# mcu_stm32h563.net
KiCad netlist of a schematic drawn in Altium Designer
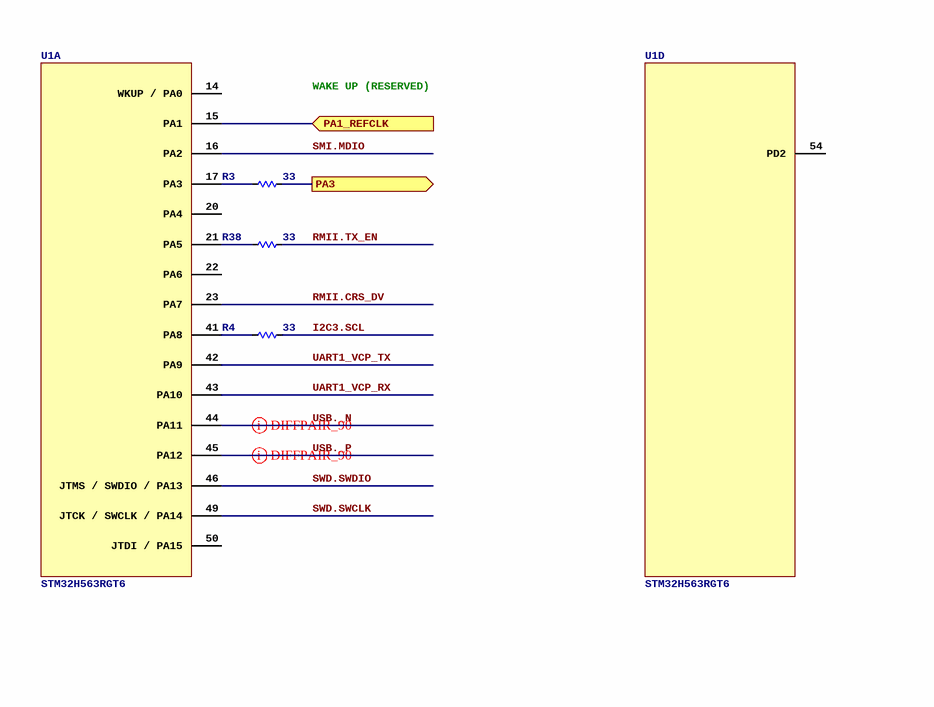
[diagram p0: mcu_stm32h563.SchDoc, top left]
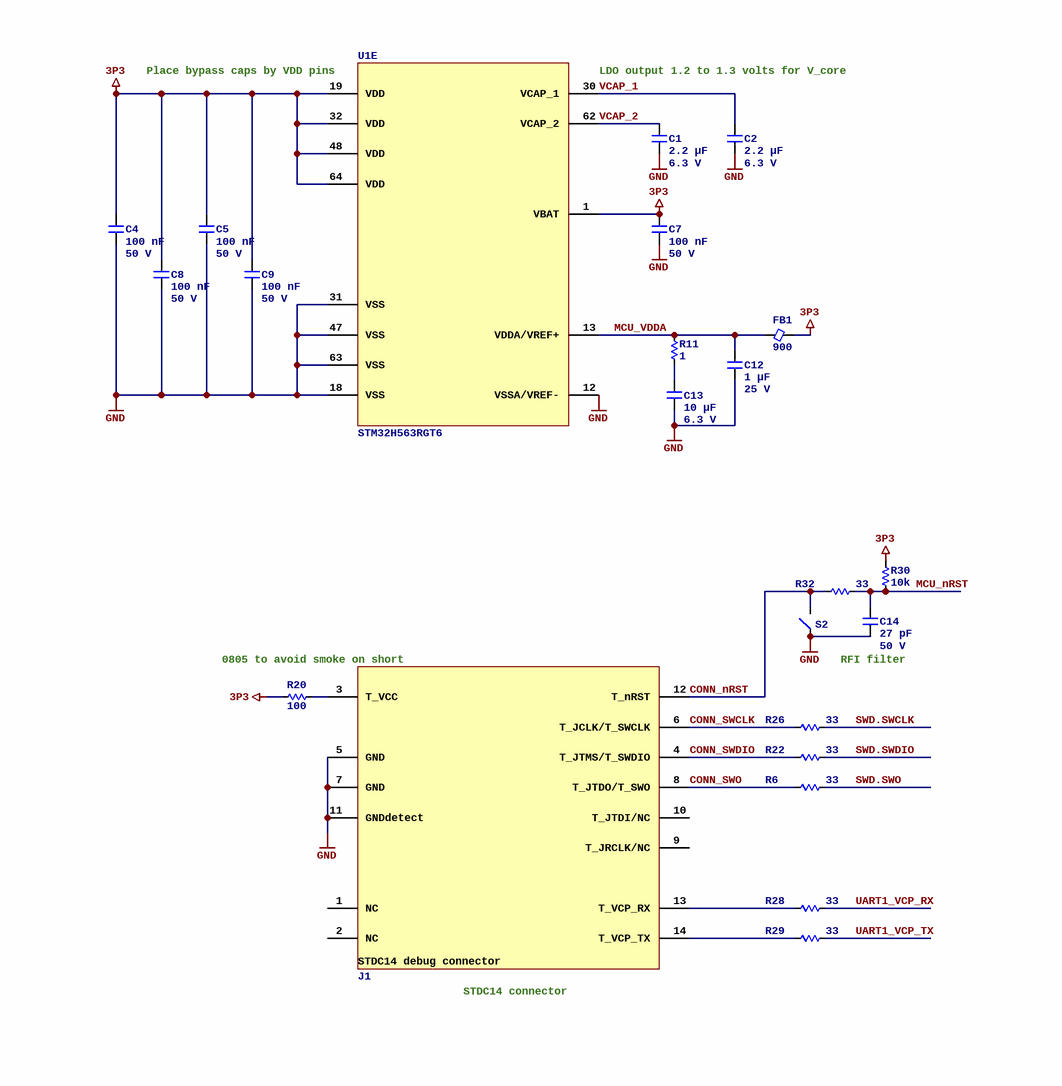
[diagram p1: mcu_stm32h563.SchDoc, top right]
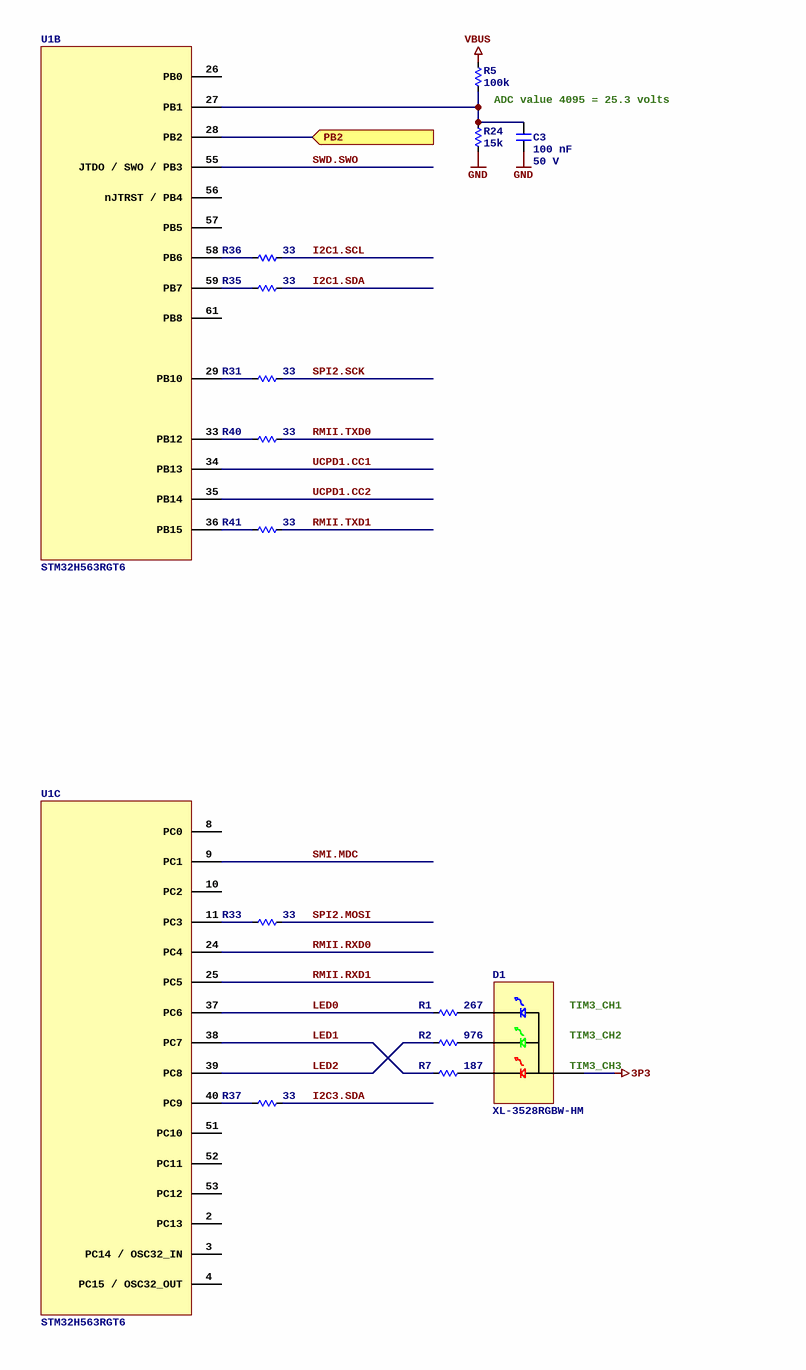
[diagram p2: mcu_stm32h563.SchDoc, bottom left]
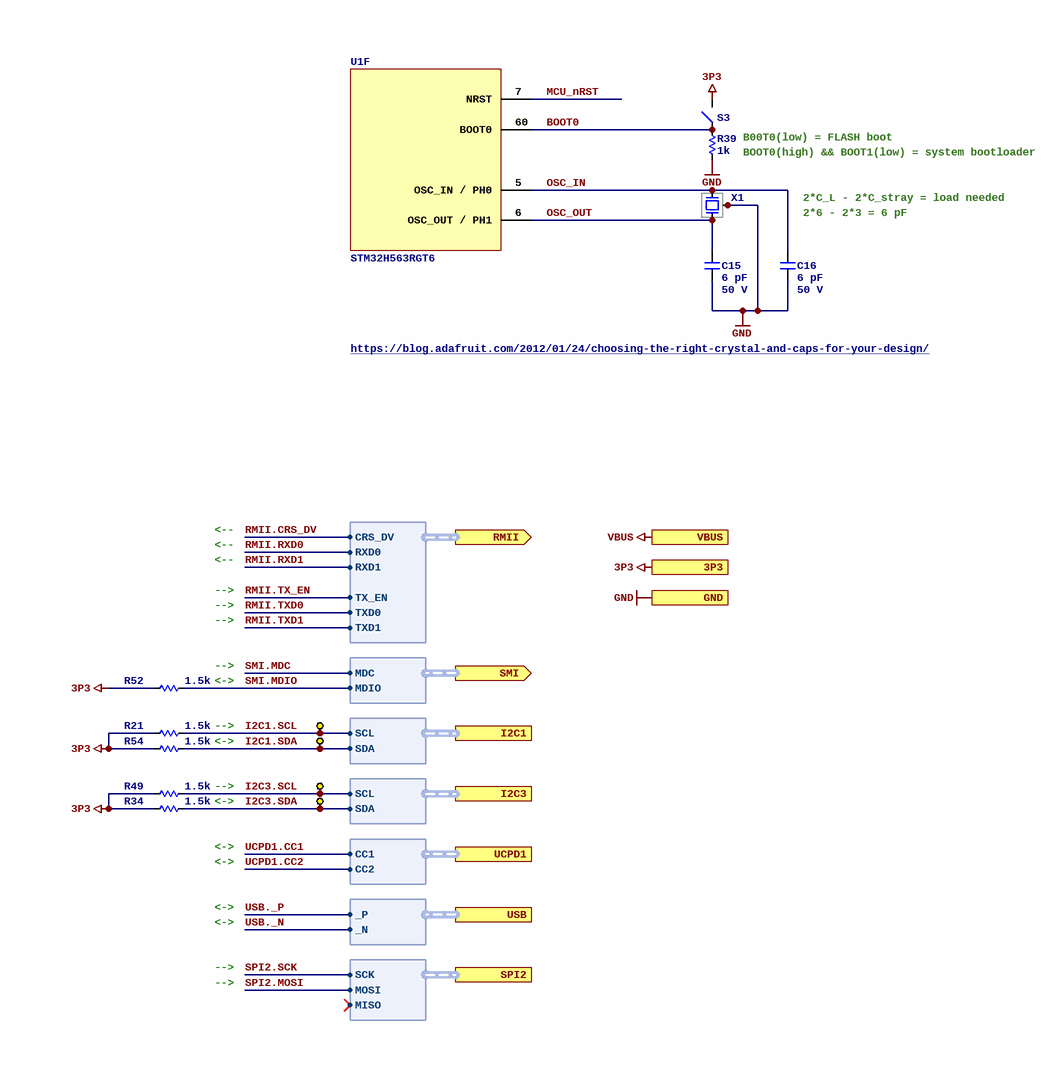
[diagram p3: mcu_stm32h563.SchDoc, bottom right]

(export (version "E")
  (design (tool "Eeschema 10.0.6"))
  (components
    (comp (ref "C1")
      (value "GCM188R70J225KE22D")
      (footprint "C0603")
      (fields
        (field (name "CAPACITANCE") "2.2 µF")
        (field (name "MANUFACTURER") "Murata Electronics")
        (field (name "VOLTAGE RATING") "6.3 V")
      )
      (libsource (lib "database") (part "__template_cap"))
    )
    (comp (ref "C2")
      (value "GCM188R70J225KE22D")
      (footprint "C0603")
      (fields
        (field (name "CAPACITANCE") "2.2 µF")
        (field (name "MANUFACTURER") "Murata Electronics")
        (field (name "VOLTAGE RATING") "6.3 V")
      )
      (libsource (lib "database") (part "__template_cap"))
    )
    (comp (ref "C3")
      (value "CL05B104KB54PNC")
      (footprint "C0402")
      (fields
        (field (name "CAPACITANCE") "100 nF")
        (field (name "MANUFACTURER") "Samsung Electro-Mechanics")
        (field (name "VOLTAGE RATING") "50 V")
      )
      (libsource (lib "database") (part "__template_cap"))
    )
    (comp (ref "C4")
      (value "CL05B104KB54PNC")
      (footprint "C0402")
      (fields
        (field (name "CAPACITANCE") "100 nF")
        (field (name "MANUFACTURER") "Samsung Electro-Mechanics")
        (field (name "VOLTAGE RATING") "50 V")
      )
      (libsource (lib "database") (part "__template_cap"))
    )
    (comp (ref "C5")
      (value "CL05B104KB54PNC")
      (footprint "C0402")
      (fields
        (field (name "CAPACITANCE") "100 nF")
        (field (name "MANUFACTURER") "Samsung Electro-Mechanics")
        (field (name "VOLTAGE RATING") "50 V")
      )
      (libsource (lib "database") (part "__template_cap"))
    )
    (comp (ref "C7")
      (value "CL05B104KB54PNC")
      (footprint "C0402")
      (fields
        (field (name "CAPACITANCE") "100 nF")
        (field (name "MANUFACTURER") "Samsung Electro-Mechanics")
        (field (name "VOLTAGE RATING") "50 V")
      )
      (libsource (lib "database") (part "__template_cap"))
    )
    (comp (ref "C8")
      (value "CL05B104KB54PNC")
      (footprint "C0402")
      (fields
        (field (name "CAPACITANCE") "100 nF")
        (field (name "MANUFACTURER") "Samsung Electro-Mechanics")
        (field (name "VOLTAGE RATING") "50 V")
      )
      (libsource (lib "database") (part "__template_cap"))
    )
    (comp (ref "C9")
      (value "CL05B104KB54PNC")
      (footprint "C0402")
      (fields
        (field (name "CAPACITANCE") "100 nF")
        (field (name "MANUFACTURER") "Samsung Electro-Mechanics")
        (field (name "VOLTAGE RATING") "50 V")
      )
      (libsource (lib "database") (part "__template_cap"))
    )
    (comp (ref "C12")
      (value "CL10B105KA8NNNC")
      (footprint "C0603")
      (fields
        (field (name "CAPACITANCE") "1 µF")
        (field (name "MANUFACTURER") "Samsung Electro-Mechanics")
        (field (name "VOLTAGE RATING") "25 V")
      )
      (libsource (lib "database") (part "__template_cap"))
    )
    (comp (ref "C13")
      (value "CC0805KKX7R5BB106")
      (footprint "C0805")
      (fields
        (field (name "CAPACITANCE") "10 µF")
        (field (name "MANUFACTURER") "YAGEO")
        (field (name "VOLTAGE RATING") "6.3 V")
      )
      (libsource (lib "database") (part "__template_cap"))
    )
    (comp (ref "C14")
      (value "CC0402JRNPO9BN270")
      (footprint "C0402")
      (fields
        (field (name "CAPACITANCE") "27 pF")
        (field (name "MANUFACTURER") "YAGEO")
        (field (name "VOLTAGE RATING") "50 V")
      )
      (libsource (lib "database") (part "__template_cap"))
    )
    (comp (ref "C15")
      (value "CC0402CRNPO9BN6R0")
      (footprint "C0402")
      (fields
        (field (name "CAPACITANCE") "6 pF")
        (field (name "MANUFACTURER") "YAGEO")
        (field (name "VOLTAGE RATING") "50 V")
      )
      (libsource (lib "database") (part "__template_cap"))
    )
    (comp (ref "C16")
      (value "CC0402CRNPO9BN6R0")
      (footprint "C0402")
      (fields
        (field (name "CAPACITANCE") "6 pF")
        (field (name "MANUFACTURER") "YAGEO")
        (field (name "VOLTAGE RATING") "50 V")
      )
      (libsource (lib "database") (part "__template_cap"))
    )
    (comp (ref "D1")
      (value "XL-3528RGBW-HM")
      (footprint "LED_RGB_SMD3528-4P")
      (description "LED Multi-Color Chip Red/Green/Blue 4-Pin PLCC T/R")
      (fields (field (name "MANUFACTURER") "XINGLIGHT"))
      (libsource (lib "database") (part "XL-3528RGBW-HM"))
    )
    (comp (ref "FB1")
      (value "BLM15PX601SN1D")
      (footprint "FB0402")
      (fields (field (name "MANUFACTURER") "Murata Electronics") (field (name "CURRENT RATING (MA)") "900"))
      (libsource (lib "database") (part "__template_fb"))
    )
    (comp (ref "J1")
      (value "FTSH-107-01-L-DV-K-A")
      (footprint "SAMTEC_FTSH-107-01-L-DV-K-A")
      (description "Connector Header Surface Mount 14 position 0.050\" (1.27mm)")
      (fields (field (name "MANUFACTURER") "Samtec"))
      (libsource (lib "database") (part "FTSH-107-01-L-DV-K-A"))
    )
    (comp (ref "R1")
      (value "267")
      (footprint "R0402")
      (fields
        (field (name "TOLERANCE") "1%")
        (field (name "MANUFACTURER PART NUMBER") "FRC0402F2670TS")
        (field (name "MANUFACTURER") "FOJAN")
      )
      (libsource (lib "database") (part "__template_resistor"))
    )
    (comp (ref "R2")
      (value "976")
      (footprint "R0402")
      (fields
        (field (name "TOLERANCE") "1%")
        (field (name "MANUFACTURER PART NUMBER") "RTT029760FTH")
        (field (name "MANUFACTURER") "RALEC")
      )
      (libsource (lib "database") (part "__template_resistor"))
    )
    (comp (ref "R3")
      (value "33")
      (footprint "R0402")
      (fields
        (field (name "TOLERANCE") "1%")
        (field (name "MANUFACTURER PART NUMBER") "CRCW040233R0FKED")
        (field (name "MANUFACTURER") "Vishay Intertech")
      )
      (libsource (lib "database") (part "__template_resistor"))
    )
    (comp (ref "R4")
      (value "33")
      (footprint "R0402")
      (fields
        (field (name "TOLERANCE") "1%")
        (field (name "MANUFACTURER PART NUMBER") "CRCW040233R0FKED")
        (field (name "MANUFACTURER") "Vishay Intertech")
      )
      (libsource (lib "database") (part "__template_resistor"))
    )
    (comp (ref "R5")
      (value "100k")
      (footprint "R0402")
      (fields
        (field (name "MANUFACTURER PART NUMBER") "0402WGF1003TCE")
        (field (name "MANUFACTURER") "UNI-ROYAL(Uniroyal Elec)")
        (field (name "TOLERANCE") "1%")
      )
      (libsource (lib "database") (part "__template_resistor"))
    )
    (comp (ref "R6")
      (value "33")
      (footprint "R0402")
      (fields
        (field (name "TOLERANCE") "1%")
        (field (name "MANUFACTURER PART NUMBER") "CRCW040233R0FKED")
        (field (name "MANUFACTURER") "Vishay Intertech")
      )
      (libsource (lib "database") (part "__template_resistor"))
    )
    (comp (ref "R7")
      (value "187")
      (footprint "R0402")
      (fields
        (field (name "TOLERANCE") "1%")
        (field (name "MANUFACTURER PART NUMBER") "ERJ2RKF1870X")
        (field (name "MANUFACTURER") "PANASONIC")
      )
      (libsource (lib "database") (part "__template_resistor"))
    )
    (comp (ref "R11")
      (value "1")
      (footprint "R0402")
      (fields
        (field (name "TOLERANCE") "1%")
        (field (name "MANUFACTURER PART NUMBER") "CRCW04021R00FKEDC")
        (field (name "MANUFACTURER") "Vishay Intertech")
      )
      (libsource (lib "database") (part "__template_resistor"))
    )
    (comp (ref "R20")
      (value "100")
      (footprint "R0805")
      (fields
        (field (name "TOLERANCE") "1%")
        (field (name "MANUFACTURER PART NUMBER") "AR05FTC1000")
        (field (name "MANUFACTURER") "Viking Tech")
      )
      (libsource (lib "database") (part "__template_resistor"))
    )
    (comp (ref "R21")
      (value "1.5k")
      (footprint "R0402")
      (fields
        (field (name "TOLERANCE") "1%")
        (field (name "MANUFACTURER PART NUMBER") "0402WGF1501TCE")
        (field (name "MANUFACTURER") "UNI-ROYAL(Uniroyal Elec)")
      )
      (libsource (lib "database") (part "__template_resistor"))
    )
    (comp (ref "R22")
      (value "33")
      (footprint "R0402")
      (fields
        (field (name "TOLERANCE") "1%")
        (field (name "MANUFACTURER PART NUMBER") "CRCW040233R0FKED")
        (field (name "MANUFACTURER") "Vishay Intertech")
      )
      (libsource (lib "database") (part "__template_resistor"))
    )
    (comp (ref "R24")
      (value "15k")
      (footprint "R0402")
      (fields
        (field (name "MANUFACTURER PART NUMBER") "0402WGF1502TCE")
        (field (name "MANUFACTURER") "UNI-ROYAL(Uniroyal Elec)")
        (field (name "TOLERANCE") "1%")
      )
      (libsource (lib "database") (part "__template_resistor"))
    )
    (comp (ref "R26")
      (value "33")
      (footprint "R0402")
      (fields
        (field (name "TOLERANCE") "1%")
        (field (name "MANUFACTURER PART NUMBER") "CRCW040233R0FKED")
        (field (name "MANUFACTURER") "Vishay Intertech")
      )
      (libsource (lib "database") (part "__template_resistor"))
    )
    (comp (ref "R28")
      (value "33")
      (footprint "R0402")
      (fields
        (field (name "TOLERANCE") "1%")
        (field (name "MANUFACTURER PART NUMBER") "CRCW040233R0FKED")
        (field (name "MANUFACTURER") "Vishay Intertech")
      )
      (libsource (lib "database") (part "__template_resistor"))
    )
    (comp (ref "R29")
      (value "33")
      (footprint "R0402")
      (fields
        (field (name "TOLERANCE") "1%")
        (field (name "MANUFACTURER PART NUMBER") "CRCW040233R0FKED")
        (field (name "MANUFACTURER") "Vishay Intertech")
      )
      (libsource (lib "database") (part "__template_resistor"))
    )
    (comp (ref "R30")
      (value "10k")
      (footprint "R0402")
      (fields
        (field (name "TOLERANCE") "1%")
        (field (name "MANUFACTURER PART NUMBER") "0402WGF1002TCE")
        (field (name "MANUFACTURER") "UNI-ROYAL(Uniroyal Elec)")
      )
      (libsource (lib "database") (part "__template_resistor"))
    )
    (comp (ref "R31")
      (value "33")
      (footprint "R0402")
      (fields
        (field (name "TOLERANCE") "1%")
        (field (name "MANUFACTURER PART NUMBER") "CRCW040233R0FKED")
        (field (name "MANUFACTURER") "Vishay Intertech")
      )
      (libsource (lib "database") (part "__template_resistor"))
    )
    (comp (ref "R32")
      (value "33")
      (footprint "R0402")
      (fields
        (field (name "TOLERANCE") "1%")
        (field (name "MANUFACTURER PART NUMBER") "CRCW040233R0FKED")
        (field (name "MANUFACTURER") "Vishay Intertech")
      )
      (libsource (lib "database") (part "__template_resistor"))
    )
    (comp (ref "R33")
      (value "33")
      (footprint "R0402")
      (fields
        (field (name "TOLERANCE") "1%")
        (field (name "MANUFACTURER PART NUMBER") "CRCW040233R0FKED")
        (field (name "MANUFACTURER") "Vishay Intertech")
      )
      (libsource (lib "database") (part "__template_resistor"))
    )
    (comp (ref "R34")
      (value "1.5k")
      (footprint "R0402")
      (fields
        (field (name "TOLERANCE") "1%")
        (field (name "MANUFACTURER PART NUMBER") "0402WGF1501TCE")
        (field (name "MANUFACTURER") "UNI-ROYAL(Uniroyal Elec)")
      )
      (libsource (lib "database") (part "__template_resistor"))
    )
    (comp (ref "R35")
      (value "33")
      (footprint "R0402")
      (fields
        (field (name "TOLERANCE") "1%")
        (field (name "MANUFACTURER PART NUMBER") "CRCW040233R0FKED")
        (field (name "MANUFACTURER") "Vishay Intertech")
      )
      (libsource (lib "database") (part "__template_resistor"))
    )
    (comp (ref "R36")
      (value "33")
      (footprint "R0402")
      (fields
        (field (name "TOLERANCE") "1%")
        (field (name "MANUFACTURER PART NUMBER") "CRCW040233R0FKED")
        (field (name "MANUFACTURER") "Vishay Intertech")
      )
      (libsource (lib "database") (part "__template_resistor"))
    )
    (comp (ref "R37")
      (value "33")
      (footprint "R0402")
      (fields
        (field (name "TOLERANCE") "1%")
        (field (name "MANUFACTURER PART NUMBER") "CRCW040233R0FKED")
        (field (name "MANUFACTURER") "Vishay Intertech")
      )
      (libsource (lib "database") (part "__template_resistor"))
    )
    (comp (ref "R38")
      (value "33")
      (footprint "R0402")
      (fields
        (field (name "TOLERANCE") "1%")
        (field (name "MANUFACTURER PART NUMBER") "CRCW040233R0FKED")
        (field (name "MANUFACTURER") "Vishay Intertech")
      )
      (libsource (lib "database") (part "__template_resistor"))
    )
    (comp (ref "R39")
      (value "1k")
      (footprint "R0402")
      (fields
        (field (name "TOLERANCE") "1%")
        (field (name "MANUFACTURER PART NUMBER") "0402WGF1001TCE")
        (field (name "MANUFACTURER") "UNI-ROYAL(Uniroyal Elec)")
      )
      (libsource (lib "database") (part "__template_resistor"))
    )
    (comp (ref "R40")
      (value "33")
      (footprint "R0402")
      (fields
        (field (name "TOLERANCE") "1%")
        (field (name "MANUFACTURER PART NUMBER") "CRCW040233R0FKED")
        (field (name "MANUFACTURER") "Vishay Intertech")
      )
      (libsource (lib "database") (part "__template_resistor"))
    )
    (comp (ref "R41")
      (value "33")
      (footprint "R0402")
      (fields
        (field (name "TOLERANCE") "1%")
        (field (name "MANUFACTURER PART NUMBER") "CRCW040233R0FKED")
        (field (name "MANUFACTURER") "Vishay Intertech")
      )
      (libsource (lib "database") (part "__template_resistor"))
    )
    (comp (ref "R49")
      (value "1.5k")
      (footprint "R0402")
      (fields
        (field (name "TOLERANCE") "1%")
        (field (name "MANUFACTURER PART NUMBER") "0402WGF1501TCE")
        (field (name "MANUFACTURER") "UNI-ROYAL(Uniroyal Elec)")
      )
      (libsource (lib "database") (part "__template_resistor"))
    )
    (comp (ref "R52")
      (value "1.5k")
      (footprint "R0402")
      (fields
        (field (name "TOLERANCE") "1%")
        (field (name "MANUFACTURER PART NUMBER") "0402WGF1501TCE")
        (field (name "MANUFACTURER") "UNI-ROYAL(Uniroyal Elec)")
      )
      (libsource (lib "database") (part "__template_resistor"))
    )
    (comp (ref "R54")
      (value "1.5k")
      (footprint "R0402")
      (fields
        (field (name "TOLERANCE") "1%")
        (field (name "MANUFACTURER PART NUMBER") "0402WGF1501TCE")
        (field (name "MANUFACTURER") "UNI-ROYAL(Uniroyal Elec)")
      )
      (libsource (lib "database") (part "__template_resistor"))
    )
    (comp (ref "S2")
      (value "TS-1092S-B3D2-G")
      (footprint "SWITCH_TS-1092S-B3D2-G")
      (description "SWITCH TACTILE SPST-NO")
      (fields (field (name "MANUFACTURER") "Yuandi"))
      (libsource (lib "database") (part "TS-1092S-B3D2-G"))
    )
    (comp (ref "S3")
      (value "TS-1092S-B3D2-G")
      (footprint "SWITCH_TS-1092S-B3D2-G")
      (description "SWITCH TACTILE SPST-NO")
      (fields (field (name "MANUFACTURER") "Yuandi"))
      (libsource (lib "database") (part "TS-1092S-B3D2-G"))
    )
    (comp (ref "TP1")
      (value "~")
      (footprint "TP_GRABBY")
      (description "EMBEDDED TEST POINT FOR SALEAE TEST CLIPS")
      (fields (field (name "MANUFACTURER PART NUMBER") "TEST_GRABBER"))
      (libsource (lib "database") (part "TEST_GRABBER"))
    )
    (comp (ref "TP2")
      (value "~")
      (footprint "TP_GRABBY")
      (description "EMBEDDED TEST POINT FOR SALEAE TEST CLIPS")
      (fields (field (name "MANUFACTURER PART NUMBER") "TEST_GRABBER"))
      (libsource (lib "database") (part "TEST_GRABBER"))
    )
    (comp (ref "TP62")
      (value "~")
      (footprint "TP_GRABBY")
      (description "EMBEDDED TEST POINT FOR SALEAE TEST CLIPS")
      (fields (field (name "MANUFACTURER PART NUMBER") "TEST_GRABBER"))
      (libsource (lib "database") (part "TEST_GRABBER"))
    )
    (comp (ref "TP63")
      (value "~")
      (footprint "TP_GRABBY")
      (description "EMBEDDED TEST POINT FOR SALEAE TEST CLIPS")
      (fields (field (name "MANUFACTURER PART NUMBER") "TEST_GRABBER"))
      (libsource (lib "database") (part "TEST_GRABBER"))
    )
    (comp (ref "U1")
      (value "STM32H563RGT6")
      (footprint "64TQFP10")
      (description "ARM® Cortex®-M33 STM32H5 Microcontroller IC 32-Bit 250MHz 1MB (1M x 8) FLASH 64-LQFP (10x10)")
      (fields
        (field (name "MANUFACTURER PART NUMBER") "STM32H563RGT6")
        (field (name "MANUFACTURER") "ST Microelectronics")
      )
      (libsource (lib "database") (part "STM32H563RGT6"))
    )
    (comp (ref "X1")
      (value "XRCGB16M000FXN00R0")
      (footprint "4_SMD_2.0X1.6MM")
      (description "CRYSTAL 16.0000MHZ 6PF SMD")
      (fields (field (name "MANUFACTURER") "Murata"))
      (libsource (lib "database") (part "__template_crystal_4pin"))
    )
  )
  (nets
    (net (code "7") (name "/BOOT0") (class "Default")
      (node (ref "R39") (pin "1") (pintype "passive"))
      (node (ref "S3") (pin "1") (pintype "passive"))
      (node (ref "U1") (pin "60") (pinfunction "BOOT0_60") (pintype "passive"))
    )
    (net (code "8") (name "/CONN_SWCLK") (class "Default")
      (node (ref "J1") (pin "6") (pinfunction "T_JCLK/T_SWCLK_6") (pintype "passive"))
      (node (ref "R26") (pin "2") (pintype "passive"))
    )
    (net (code "9") (name "/CONN_SWDIO") (class "Default")
      (node (ref "J1") (pin "4") (pinfunction "T_JTMS/T_SWDIO_4") (pintype "passive"))
      (node (ref "R22") (pin "2") (pintype "passive"))
    )
    (net (code "10") (name "/CONN_SWO") (class "Default")
      (node (ref "J1") (pin "8") (pinfunction "T_JTDO/T_SWO_8") (pintype "passive"))
      (node (ref "R6") (pin "2") (pintype "passive"))
    )
    (net (code "11") (name "/CONN_nRST") (class "Default")
      (node (ref "J1") (pin "12") (pinfunction "T_nRST_12") (pintype "passive"))
      (node (ref "R32") (pin "2") (pintype "passive"))
      (node (ref "S2") (pin "2") (pintype "passive"))
    )
    (net (code "12") (name "/I2C1.SCL") (class "Default")
      (node (ref "R21") (pin "1") (pintype "passive"))
      (node (ref "R36") (pin "1") (pintype "passive"))
      (node (ref "TP62") (pin "1") (pintype "passive"))
    )
    (net (code "13") (name "/I2C1.SDA") (class "Default")
      (node (ref "R35") (pin "1") (pintype "passive"))
      (node (ref "R54") (pin "1") (pintype "passive"))
      (node (ref "TP63") (pin "1") (pintype "passive"))
    )
    (net (code "14") (name "/I2C3.SCL") (class "Default")
      (node (ref "R4") (pin "1") (pintype "passive"))
      (node (ref "R49") (pin "1") (pintype "passive"))
      (node (ref "TP1") (pin "1") (pintype "passive"))
    )
    (net (code "15") (name "/I2C3.SDA") (class "Default")
      (node (ref "R34") (pin "1") (pintype "passive"))
      (node (ref "R37") (pin "1") (pintype "passive"))
      (node (ref "TP2") (pin "1") (pintype "passive"))
    )
    (net (code "16") (name "/LED0") (class "Default")
      (node (ref "R1") (pin "2") (pintype "passive"))
      (node (ref "U1") (pin "37") (pinfunction "PC6_37") (pintype "passive"))
    )
    (net (code "17") (name "/LED1") (class "Default")
      (node (ref "R7") (pin "2") (pintype "passive"))
      (node (ref "U1") (pin "38") (pinfunction "PC7_38") (pintype "passive"))
    )
    (net (code "18") (name "/LED2") (class "Default")
      (node (ref "R2") (pin "2") (pintype "passive"))
      (node (ref "U1") (pin "39") (pinfunction "PC8_39") (pintype "passive"))
    )
    (net (code "19") (name "/MCU_VDDA") (class "Default")
      (node (ref "C12") (pin "1") (pintype "passive"))
      (node (ref "FB1") (pin "1") (pintype "passive"))
      (node (ref "R11") (pin "2") (pintype "passive"))
      (node (ref "U1") (pin "13") (pinfunction "VDDA/VREF+_13") (pintype "passive"))
    )
    (net (code "20") (name "/MCU_nRST") (class "Default")
      (node (ref "C14") (pin "1") (pintype "passive"))
      (node (ref "R30") (pin "2") (pintype "passive"))
      (node (ref "R32") (pin "1") (pintype "passive"))
      (node (ref "U1") (pin "7") (pinfunction "NRST_7") (pintype "passive"))
    )
    (net (code "21") (name "/OSC_IN") (class "Default")
      (node (ref "C16") (pin "1") (pintype "passive"))
      (node (ref "U1") (pin "5") (pinfunction "OSC_IN_/_PH0_5") (pintype "passive"))
      (node (ref "X1") (pin "3") (pinfunction "3_3") (pintype "passive"))
    )
    (net (code "22") (name "/OSC_OUT") (class "Default")
      (node (ref "C15") (pin "1") (pintype "passive"))
      (node (ref "U1") (pin "6") (pinfunction "OSC_OUT_/_PH1_6") (pintype "passive"))
      (node (ref "X1") (pin "1") (pinfunction "1_1") (pintype "passive"))
    )
    (net (code "23") (name "/PA1_REFCLK") (class "Default")
      (node (ref "U1") (pin "15") (pinfunction "PA1_15") (pintype "passive"))
    )
    (net (code "24") (name "/PA3") (class "Default") (node (ref "R3") (pin "1") (pintype "passive")))
    (net (code "25") (name "/PB2") (class "Default")
      (node (ref "U1") (pin "28") (pinfunction "PB2_28") (pintype "passive"))
    )
    (net (code "26") (name "/RMII.CRS_DV") (class "Default")
      (node (ref "U1") (pin "23") (pinfunction "PA7_23") (pintype "passive"))
    )
    (net (code "27") (name "/RMII.RXD0") (class "Default")
      (node (ref "U1") (pin "24") (pinfunction "PC4_24") (pintype "passive"))
    )
    (net (code "28") (name "/RMII.RXD1") (class "Default")
      (node (ref "U1") (pin "25") (pinfunction "PC5_25") (pintype "passive"))
    )
    (net (code "29") (name "/RMII.TXD0") (class "Default") (node (ref "R40") (pin "1") (pintype "passive")))
    (net (code "30") (name "/RMII.TXD1") (class "Default") (node (ref "R41") (pin "1") (pintype "passive")))
    (net (code "31") (name "/RMII.TX_EN") (class "Default") (node (ref "R38") (pin "1") (pintype "passive")))
    (net (code "32") (name "/SMI.MDC") (class "Default")
      (node (ref "U1") (pin "9") (pinfunction "PC1_9") (pintype "passive"))
    )
    (net (code "33") (name "/SMI.MDIO") (class "Default")
      (node (ref "R52") (pin "1") (pintype "passive"))
      (node (ref "U1") (pin "16") (pinfunction "PA2_16") (pintype "passive"))
    )
    (net (code "34") (name "/SPI2.MOSI") (class "Default") (node (ref "R33") (pin "1") (pintype "passive")))
    (net (code "35") (name "/SPI2.SCK") (class "Default") (node (ref "R31") (pin "1") (pintype "passive")))
    (net (code "36") (name "/SWD.SWCLK") (class "Default")
      (node (ref "R26") (pin "1") (pintype "passive"))
      (node (ref "U1") (pin "49") (pinfunction "JTCK_/_SWCLK_/_PA14_49") (pintype "passive"))
    )
    (net (code "37") (name "/SWD.SWDIO") (class "Default")
      (node (ref "R22") (pin "1") (pintype "passive"))
      (node (ref "U1") (pin "46") (pinfunction "JTMS_/_SWDIO_/_PA13_46") (pintype "passive"))
    )
    (net (code "38") (name "/SWD.SWO") (class "Default")
      (node (ref "R6") (pin "1") (pintype "passive"))
      (node (ref "U1") (pin "55") (pinfunction "JTDO_/_SWO_/_PB3_55") (pintype "passive"))
    )
    (net (code "39") (name "/UART1_VCP_RX") (class "Default")
      (node (ref "R28") (pin "1") (pintype "passive"))
      (node (ref "U1") (pin "43") (pinfunction "PA10_43") (pintype "passive"))
    )
    (net (code "40") (name "/UART1_VCP_TX") (class "Default")
      (node (ref "R29") (pin "1") (pintype "passive"))
      (node (ref "U1") (pin "42") (pinfunction "PA9_42") (pintype "passive"))
    )
    (net (code "41") (name "/UCPD1.CC1") (class "Default")
      (node (ref "U1") (pin "34") (pinfunction "PB13_34") (pintype "passive"))
    )
    (net (code "42") (name "/UCPD1.CC2") (class "Default")
      (node (ref "U1") (pin "35") (pinfunction "PB14_35") (pintype "passive"))
    )
    (net (code "43") (name "/USB._N") (class "Default")
      (node (ref "U1") (pin "44") (pinfunction "PA11_44") (pintype "passive"))
    )
    (net (code "44") (name "/USB._P") (class "Default")
      (node (ref "U1") (pin "45") (pinfunction "PA12_45") (pintype "passive"))
    )
    (net (code "45") (name "/VCAP_1") (class "Default")
      (node (ref "C2") (pin "1") (pintype "passive"))
      (node (ref "U1") (pin "30") (pinfunction "VCAP_1_30") (pintype "passive"))
    )
    (net (code "46") (name "/VCAP_2") (class "Default")
      (node (ref "C1") (pin "1") (pintype "passive"))
      (node (ref "U1") (pin "62") (pinfunction "VCAP_2_62") (pintype "passive"))
    )
    (net (code "53") (name "3P3") (class "Default")
      (node (ref "C4") (pin "1") (pintype "passive"))
      (node (ref "C5") (pin "1") (pintype "passive"))
      (node (ref "C7") (pin "1") (pintype "passive"))
      (node (ref "C8") (pin "1") (pintype "passive"))
      (node (ref "C9") (pin "1") (pintype "passive"))
      (node (ref "D1") (pin "2") (pintype "passive"))
      (node (ref "FB1") (pin "2") (pintype "passive"))
      (node (ref "R20") (pin "2") (pintype "passive"))
      (node (ref "R21") (pin "2") (pintype "passive"))
      (node (ref "R30") (pin "1") (pintype "passive"))
      (node (ref "R34") (pin "2") (pintype "passive"))
      (node (ref "R49") (pin "2") (pintype "passive"))
      (node (ref "R52") (pin "2") (pintype "passive"))
      (node (ref "R54") (pin "2") (pintype "passive"))
      (node (ref "S3") (pin "2") (pintype "passive"))
      (node (ref "U1") (pin "1") (pinfunction "VBAT_1") (pintype "passive"))
      (node (ref "U1") (pin "19") (pinfunction "VDD_19") (pintype "passive"))
      (node (ref "U1") (pin "32") (pinfunction "VDD_32") (pintype "passive"))
      (node (ref "U1") (pin "48") (pinfunction "VDD_48") (pintype "passive"))
      (node (ref "U1") (pin "64") (pinfunction "VDD_64") (pintype "passive"))
    )
    (net (code "54") (name "GND") (class "Default")
      (node (ref "C1") (pin "2") (pintype "passive"))
      (node (ref "C12") (pin "2") (pintype "passive"))
      (node (ref "C13") (pin "2") (pintype "passive"))
      (node (ref "C14") (pin "2") (pintype "passive"))
      (node (ref "C15") (pin "2") (pintype "passive"))
      (node (ref "C16") (pin "2") (pintype "passive"))
      (node (ref "C2") (pin "2") (pintype "passive"))
      (node (ref "C3") (pin "2") (pintype "passive"))
      (node (ref "C4") (pin "2") (pintype "passive"))
      (node (ref "C5") (pin "2") (pintype "passive"))
      (node (ref "C7") (pin "2") (pintype "passive"))
      (node (ref "C8") (pin "2") (pintype "passive"))
      (node (ref "C9") (pin "2") (pintype "passive"))
      (node (ref "J1") (pin "11") (pinfunction "GNDdetect_11") (pintype "passive"))
      (node (ref "J1") (pin "5") (pinfunction "GND_5") (pintype "passive"))
      (node (ref "J1") (pin "7") (pinfunction "GND_7") (pintype "passive"))
      (node (ref "R24") (pin "1") (pintype "passive"))
      (node (ref "R39") (pin "2") (pintype "passive"))
      (node (ref "S2") (pin "1") (pintype "passive"))
      (node (ref "U1") (pin "12") (pinfunction "VSSA/VREF-_12") (pintype "passive"))
      (node (ref "U1") (pin "18") (pinfunction "VSS_18") (pintype "passive"))
      (node (ref "U1") (pin "31") (pinfunction "VSS_31") (pintype "passive"))
      (node (ref "U1") (pin "47") (pinfunction "VSS_47") (pintype "passive"))
      (node (ref "U1") (pin "63") (pinfunction "VSS_63") (pintype "passive"))
      (node (ref "X1") (pin "2") (pinfunction "2_2") (pintype "passive"))
      (node (ref "X1") (pin "4") (pinfunction "4_4") (pintype "passive"))
    )
    (net (code "55") (name "Net-(C13-Pad1)") (class "Default")
      (node (ref "C13") (pin "1") (pintype "passive"))
      (node (ref "R11") (pin "1") (pintype "passive"))
    )
    (net (code "56") (name "Net-(D1-Pad1)") (class "Default")
      (node (ref "D1") (pin "1") (pintype "passive"))
      (node (ref "R7") (pin "1") (pintype "passive"))
    )
    (net (code "57") (name "Net-(D1-Pad3)") (class "Default")
      (node (ref "D1") (pin "3") (pintype "passive"))
      (node (ref "R2") (pin "1") (pintype "passive"))
    )
    (net (code "58") (name "Net-(D1-Pad4)") (class "Default")
      (node (ref "D1") (pin "4") (pintype "passive"))
      (node (ref "R1") (pin "1") (pintype "passive"))
    )
    (net (code "59") (name "Net-(J1-T_VCC)") (class "Default")
      (node (ref "J1") (pin "3") (pinfunction "T_VCC_3") (pintype "passive"))
      (node (ref "R20") (pin "1") (pintype "passive"))
    )
    (net (code "60") (name "Net-(J1-T_VCP_RX)") (class "Default")
      (node (ref "J1") (pin "13") (pinfunction "T_VCP_RX_13") (pintype "passive"))
      (node (ref "R28") (pin "2") (pintype "passive"))
    )
    (net (code "61") (name "Net-(J1-T_VCP_TX)") (class "Default")
      (node (ref "J1") (pin "14") (pinfunction "T_VCP_TX_14") (pintype "passive"))
      (node (ref "R29") (pin "2") (pintype "passive"))
    )
    (net (code "62") (name "Net-(U1A-PA3)") (class "Default")
      (node (ref "R3") (pin "2") (pintype "passive"))
      (node (ref "U1") (pin "17") (pinfunction "PA3_17") (pintype "passive"))
    )
    (net (code "63") (name "Net-(U1A-PA5)") (class "Default")
      (node (ref "R38") (pin "2") (pintype "passive"))
      (node (ref "U1") (pin "21") (pinfunction "PA5_21") (pintype "passive"))
    )
    (net (code "64") (name "Net-(U1A-PA8)") (class "Default")
      (node (ref "R4") (pin "2") (pintype "passive"))
      (node (ref "U1") (pin "41") (pinfunction "PA8_41") (pintype "passive"))
    )
    (net (code "65") (name "Net-(U1B-PB1)") (class "Default")
      (node (ref "C3") (pin "1") (pintype "passive"))
      (node (ref "R24") (pin "2") (pintype "passive"))
      (node (ref "R5") (pin "1") (pintype "passive"))
      (node (ref "U1") (pin "27") (pinfunction "PB1_27") (pintype "passive"))
    )
    (net (code "66") (name "Net-(U1B-PB6)") (class "Default")
      (node (ref "R36") (pin "2") (pintype "passive"))
      (node (ref "U1") (pin "58") (pinfunction "PB6_58") (pintype "passive"))
    )
    (net (code "67") (name "Net-(U1B-PB7)") (class "Default")
      (node (ref "R35") (pin "2") (pintype "passive"))
      (node (ref "U1") (pin "59") (pinfunction "PB7_59") (pintype "passive"))
    )
    (net (code "68") (name "Net-(U1B-PB10)") (class "Default")
      (node (ref "R31") (pin "2") (pintype "passive"))
      (node (ref "U1") (pin "29") (pinfunction "PB10_29") (pintype "passive"))
    )
    (net (code "69") (name "Net-(U1B-PB12)") (class "Default")
      (node (ref "R40") (pin "2") (pintype "passive"))
      (node (ref "U1") (pin "33") (pinfunction "PB12_33") (pintype "passive"))
    )
    (net (code "70") (name "Net-(U1B-PB15)") (class "Default")
      (node (ref "R41") (pin "2") (pintype "passive"))
      (node (ref "U1") (pin "36") (pinfunction "PB15_36") (pintype "passive"))
    )
    (net (code "71") (name "Net-(U1C-PC3)") (class "Default")
      (node (ref "R33") (pin "2") (pintype "passive"))
      (node (ref "U1") (pin "11") (pinfunction "PC3_11") (pintype "passive"))
    )
    (net (code "72") (name "Net-(U1C-PC9)") (class "Default")
      (node (ref "R37") (pin "2") (pintype "passive"))
      (node (ref "U1") (pin "40") (pinfunction "PC9_40") (pintype "passive"))
    )
    (net (code "73") (name "VBUS") (class "Default") (node (ref "R5") (pin "2") (pintype "passive")))
    (net (code "74") (name "unconnected-(J1-NC-Pad1)") (class "Default")
      (node (ref "J1") (pin "1") (pinfunction "NC_1") (pintype "passive"))
    )
    (net (code "75") (name "unconnected-(J1-NC-Pad2)") (class "Default")
      (node (ref "J1") (pin "2") (pinfunction "NC_2") (pintype "passive"))
    )
    (net (code "76") (name "unconnected-(J1-T_JRCLK{slash}NC-Pad9)") (class "Default")
      (node (ref "J1") (pin "9") (pinfunction "T_JRCLK/NC_9") (pintype "passive"))
    )
    (net (code "77") (name "unconnected-(J1-T_JTDI{slash}NC-Pad10)") (class "Default")
      (node (ref "J1") (pin "10") (pinfunction "T_JTDI/NC_10") (pintype "passive"))
    )
    (net (code "78") (name "unconnected-(U1A-JTDI_{slash}_PA15-Pad50)") (class "Default")
      (node (ref "U1") (pin "50") (pinfunction "JTDI_/_PA15_50") (pintype "passive"))
    )
    (net (code "79") (name "unconnected-(U1A-PA4-Pad20)") (class "Default")
      (node (ref "U1") (pin "20") (pinfunction "PA4_20") (pintype "passive"))
    )
    (net (code "80") (name "unconnected-(U1A-PA6-Pad22)") (class "Default")
      (node (ref "U1") (pin "22") (pinfunction "PA6_22") (pintype "passive"))
    )
    (net (code "81") (name "unconnected-(U1A-WKUP_{slash}_PA0-Pad14)") (class "Default")
      (node (ref "U1") (pin "14") (pinfunction "WKUP_/_PA0_14") (pintype "passive"))
    )
    (net (code "82") (name "unconnected-(U1B-PB0-Pad26)") (class "Default")
      (node (ref "U1") (pin "26") (pinfunction "PB0_26") (pintype "passive"))
    )
    (net (code "83") (name "unconnected-(U1B-PB5-Pad57)") (class "Default")
      (node (ref "U1") (pin "57") (pinfunction "PB5_57") (pintype "passive"))
    )
    (net (code "84") (name "unconnected-(U1B-PB8-Pad61)") (class "Default")
      (node (ref "U1") (pin "61") (pinfunction "PB8_61") (pintype "passive"))
    )
    (net (code "85") (name "unconnected-(U1B-nJTRST_{slash}_PB4-Pad56)") (class "Default")
      (node (ref "U1") (pin "56") (pinfunction "nJTRST_/_PB4_56") (pintype "passive"))
    )
    (net (code "86") (name "unconnected-(U1C-PC0-Pad8)") (class "Default")
      (node (ref "U1") (pin "8") (pinfunction "PC0_8") (pintype "passive"))
    )
    (net (code "87") (name "unconnected-(U1C-PC2-Pad10)") (class "Default")
      (node (ref "U1") (pin "10") (pinfunction "PC2_10") (pintype "passive"))
    )
    (net (code "88") (name "unconnected-(U1C-PC10-Pad51)") (class "Default")
      (node (ref "U1") (pin "51") (pinfunction "PC10_51") (pintype "passive"))
    )
    (net (code "89") (name "unconnected-(U1C-PC11-Pad52)") (class "Default")
      (node (ref "U1") (pin "52") (pinfunction "PC11_52") (pintype "passive"))
    )
    (net (code "90") (name "unconnected-(U1C-PC12-Pad53)") (class "Default")
      (node (ref "U1") (pin "53") (pinfunction "PC12_53") (pintype "passive"))
    )
    (net (code "91") (name "unconnected-(U1C-PC13-Pad2)") (class "Default")
      (node (ref "U1") (pin "2") (pinfunction "PC13_2") (pintype "passive"))
    )
    (net (code "92") (name "unconnected-(U1C-PC14_{slash}_OSC32_IN-Pad3)") (class "Default")
      (node (ref "U1") (pin "3") (pinfunction "PC14_/_OSC32_IN_3") (pintype "passive"))
    )
    (net (code "93") (name "unconnected-(U1C-PC15_{slash}_OSC32_OUT-Pad4)") (class "Default")
      (node (ref "U1") (pin "4") (pinfunction "PC15_/_OSC32_OUT_4") (pintype "passive"))
    )
    (net (code "94") (name "unconnected-(U1D-PD2-Pad54)") (class "Default")
      (node (ref "U1") (pin "54") (pinfunction "PD2_54") (pintype "passive"))
    )
  )
)
